# AUDIO_AMP_PT2300.net
KiCad netlist of a schematic drawn in Altium Designer
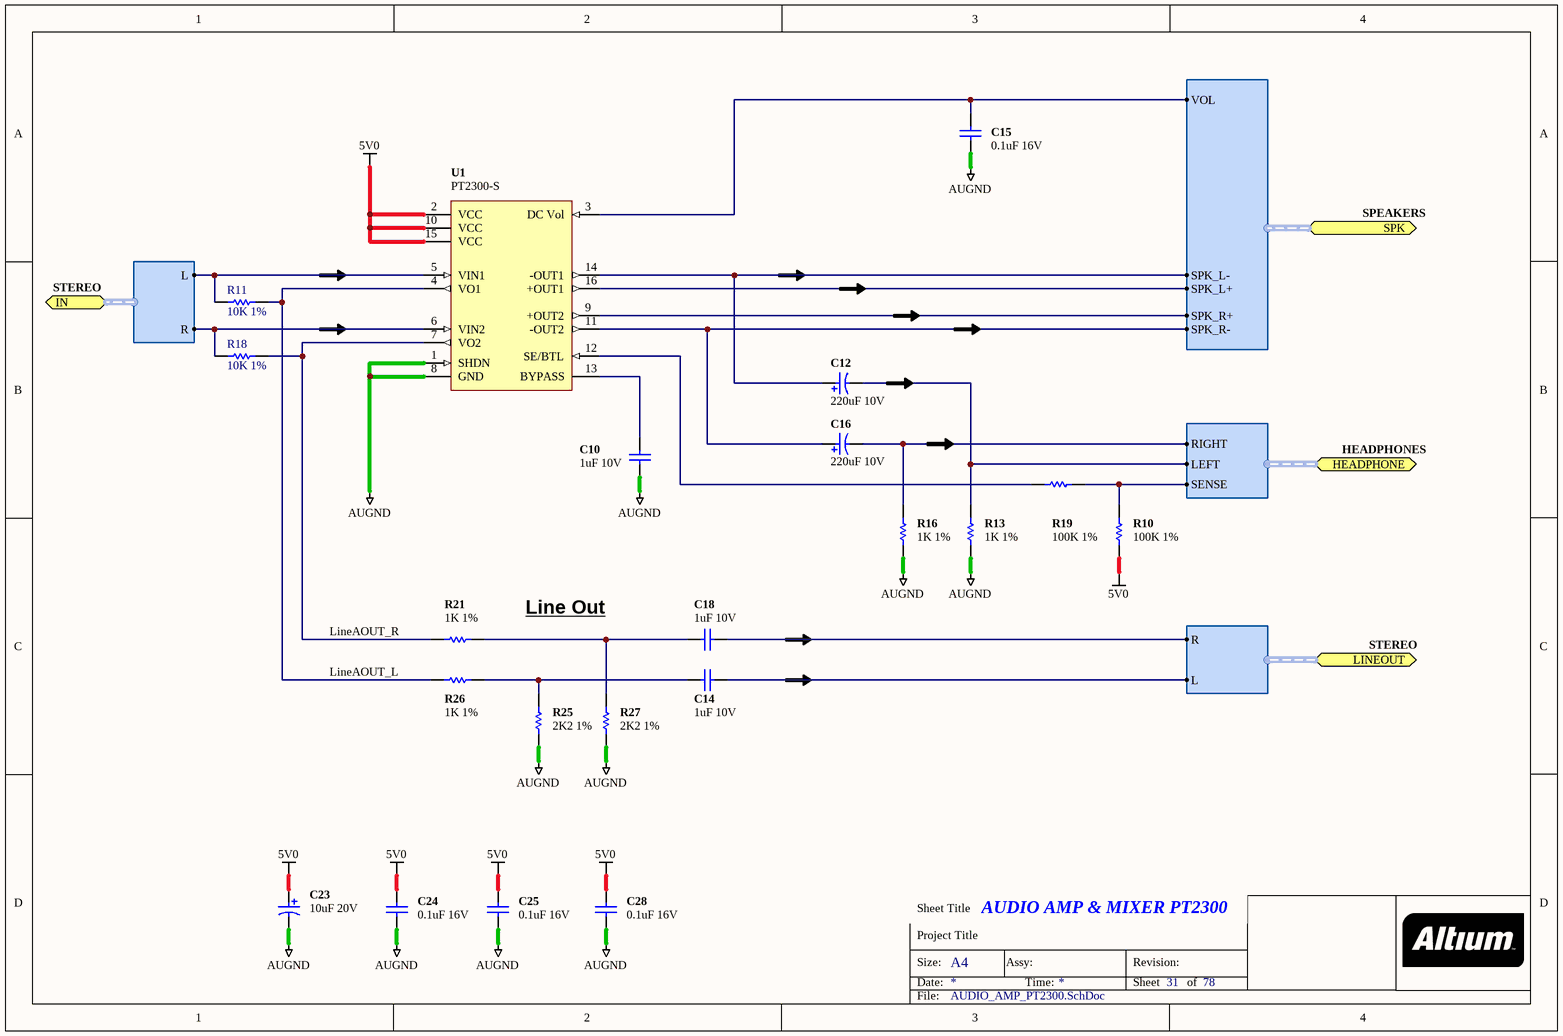
[diagram p0: AUDIO_AMP_PT2300.SchDoc]

(export (version "E")
  (design (tool "Eeschema 10.0.6"))
  (components
    (comp (ref "C10")
      (value "1uF 10V")
      (footprint "CAPC1005-STAR")
      (description "Capacitor, Ceramic, 1uF 10% 10V 0402 (1005) X5R")
      (fields (field (name "TOLERANCE") "10 %"))
      (libsource (lib "AltiumDesignLibrary") (part "CAP-NP"))
    )
    (comp (ref "C12")
      (value "220uF 10V")
      (footprint "CAPC7343-STAR")
      (description "Capacitor, Tantalum, 220uF 10% 10V MCCT-D (7343-31)")
      (fields (field (name "TOLERANCE") "10 %"))
      (libsource (lib "altium-import") (part "root_1_CAP-P_"))
    )
    (comp (ref "C14")
      (value "1uF 10V")
      (footprint "CAPC1005-STAR")
      (description "Capacitor, Ceramic, 1uF 10% 10V 0402 (1005) X5R")
      (fields (field (name "TOLERANCE") "10 %"))
      (libsource (lib "AltiumDesignLibrary") (part "CAP-NP"))
    )
    (comp (ref "C15")
      (value "0.1uF 16V")
      (footprint "CAPC1005-STAR")
      (description "Capacitor, Ceramic, 0.1uF 10% 16V 0402 (1005) X7R")
      (fields (field (name "TOLERANCE") "10 %"))
      (libsource (lib "altium-import") (part "root_2_CAP-NP_"))
    )
    (comp (ref "C16")
      (value "220uF 10V")
      (footprint "CAPC7343-STAR")
      (description "Capacitor, Tantalum, 220uF 10% 10V MCCT-D (7343-31)")
      (fields (field (name "TOLERANCE") "10 %"))
      (libsource (lib "altium-import") (part "root_1_CAP-P_"))
    )
    (comp (ref "C18")
      (value "1uF 10V")
      (footprint "CAPC1005-STAR")
      (description "Capacitor, Ceramic, 1uF 10% 10V 0402 (1005) X5R")
      (fields (field (name "TOLERANCE") "10 %"))
      (libsource (lib "AltiumDesignLibrary") (part "CAP-NP"))
    )
    (comp (ref "C23")
      (value "10uF 20V")
      (footprint "CAPC3528-STAR")
      (description "Capacitor, Tantalum, 10uF 10% 20V MCCT-B (3528)")
      (fields (field (name "TOLERANCE") "10 %"))
      (libsource (lib "altium-import") (part "root_0_mirrored_CAP-P_"))
    )
    (comp (ref "C24")
      (value "0.1uF 16V")
      (footprint "CAPC1005-STAR")
      (description "Capacitor, Ceramic, 0.1uF 10% 16V 0402 (1005) X7R")
      (fields (field (name "TOLERANCE") "10 %"))
      (libsource (lib "altium-import") (part "root_2_CAP-NP_"))
    )
    (comp (ref "C25")
      (value "0.1uF 16V")
      (footprint "CAPC1005-STAR")
      (description "Capacitor, Ceramic, 0.1uF 10% 16V 0402 (1005) X7R")
      (fields (field (name "TOLERANCE") "10 %"))
      (libsource (lib "altium-import") (part "root_2_CAP-NP_"))
    )
    (comp (ref "C28")
      (value "0.1uF 16V")
      (footprint "CAPC1005-STAR")
      (description "Capacitor, Ceramic, 0.1uF 10% 16V 0402 (1005) X7R")
      (fields (field (name "TOLERANCE") "10 %"))
      (libsource (lib "altium-import") (part "root_2_CAP-NP_"))
    )
    (comp (ref "R10")
      (value "100K 1%")
      (footprint "RESC1005-STAR")
      (description "Resistor, 100K 1% 0402 (1005)")
      (fields (field (name "TOLERANCE") "1 %"))
      (libsource (lib "altium-import") (part "root_0_RES_"))
    )
    (comp (ref "R11")
      (value "10K 1%")
      (footprint "RESC1005-STAR")
      (description "Resistor, 10K 1% 0402 (1005)")
      (fields (field (name "TOLERANCE") "1%"))
      (libsource (lib "AltiumDesignLibrary") (part "RES"))
    )
    (comp (ref "R13")
      (value "1K 1%")
      (footprint "RESC1005-STAR")
      (description "Resistor, 1K 1% 0402 (1005)")
      (fields (field (name "TOLERANCE") "1 %"))
      (libsource (lib "altium-import") (part "root_2_RES_"))
    )
    (comp (ref "R16")
      (value "1K 1%")
      (footprint "RESC1005-STAR")
      (description "Resistor, 1K 1% 0402 (1005)")
      (fields (field (name "TOLERANCE") "1 %"))
      (libsource (lib "altium-import") (part "root_2_RES_"))
    )
    (comp (ref "R18")
      (value "10K 1%")
      (footprint "RESC1005-STAR")
      (description "Resistor, 10K 1% 0402 (1005)")
      (fields (field (name "TOLERANCE") "1%"))
      (libsource (lib "AltiumDesignLibrary") (part "RES"))
    )
    (comp (ref "R19")
      (value "100K 1%")
      (footprint "RESC1005-STAR")
      (description "Resistor, 100K 1% 0402 (1005)")
      (fields (field (name "TOLERANCE") "1 %"))
      (libsource (lib "altium-import") (part "root_1_RES_"))
    )
    (comp (ref "R21")
      (value "1K 1%")
      (footprint "RESC1005-STAR")
      (description "Resistor, 1K 1% 0402 (1005)")
      (fields (field (name "TOLERANCE") "1 %"))
      (libsource (lib "altium-import") (part "root_1_RES_"))
    )
    (comp (ref "R25")
      (value "2K2 1%")
      (footprint "RESC1005-STAR")
      (description "Resistor, 2K2 1% 0402 (1005)")
      (fields (field (name "TOLERANCE") "1 %"))
      (libsource (lib "altium-import") (part "root_2_RES_"))
    )
    (comp (ref "R26")
      (value "1K 1%")
      (footprint "RESC1005-STAR")
      (description "Resistor, 1K 1% 0402 (1005)")
      (fields (field (name "TOLERANCE") "1 %"))
      (libsource (lib "altium-import") (part "root_1_RES_"))
    )
    (comp (ref "R27")
      (value "2K2 1%")
      (footprint "RESC1005-STAR")
      (description "Resistor, 2K2 1% 0402 (1005)")
      (fields (field (name "TOLERANCE") "1 %"))
      (libsource (lib "altium-import") (part "root_0_RES_"))
    )
    (comp (ref "U1")
      (value "PT2300-S")
      (footprint "SOIC127P1030-16N")
      (description "PT2300, 2W x 2 Class AB Audio Power Amplifier")
      (libsource (lib "AltiumDesignLibrary") (part "PT2300-16"))
    )
  )
  (nets
    (net (code "4") (name "/LEFT") (class "Default")
      (node (ref "C12") (pin "2") (pinfunction "2_2") (pintype "passive"))
      (node (ref "R13") (pin "2") (pinfunction "2_2") (pintype "passive"))
    )
    (net (code "5") (name "/LineAOUT_L") (class "Default")
      (node (ref "R11") (pin "2") (pinfunction "2_2") (pintype "passive"))
      (node (ref "R26") (pin "1") (pinfunction "1_1") (pintype "passive"))
      (node (ref "U1") (pin "4") (pinfunction "VO1_4") (pintype "output"))
    )
    (net (code "6") (name "/LineAOUT_R") (class "Default")
      (node (ref "R18") (pin "2") (pinfunction "2_2") (pintype "passive"))
      (node (ref "R21") (pin "1") (pinfunction "1_1") (pintype "passive"))
      (node (ref "U1") (pin "7") (pinfunction "VO2_7") (pintype "output"))
    )
    (net (code "7") (name "/RIGHT") (class "Default")
      (node (ref "C16") (pin "2") (pinfunction "2_2") (pintype "passive"))
      (node (ref "R16") (pin "2") (pinfunction "2_2") (pintype "passive"))
    )
    (net (code "8") (name "/SENSE") (class "Default")
      (node (ref "R10") (pin "1") (pinfunction "1_1") (pintype "passive"))
      (node (ref "R19") (pin "2") (pinfunction "2_2") (pintype "passive"))
    )
    (net (code "9") (name "/SPK_L+") (class "Default")
      (node (ref "U1") (pin "16") (pinfunction "+OUT1_16") (pintype "output"))
    )
    (net (code "10") (name "/SPK_L-") (class "Default")
      (node (ref "C12") (pin "1") (pinfunction "1_1") (pintype "passive"))
      (node (ref "U1") (pin "14") (pinfunction "-OUT1_14") (pintype "output"))
    )
    (net (code "11") (name "/SPK_R+") (class "Default")
      (node (ref "U1") (pin "9") (pinfunction "+OUT2_9") (pintype "output"))
    )
    (net (code "12") (name "/SPK_R-") (class "Default")
      (node (ref "C16") (pin "1") (pinfunction "1_1") (pintype "passive"))
      (node (ref "U1") (pin "11") (pinfunction "-OUT2_11") (pintype "output"))
    )
    (net (code "13") (name "/VOL") (class "Default")
      (node (ref "C15") (pin "2") (pinfunction "2_2") (pintype "passive"))
      (node (ref "U1") (pin "3") (pinfunction "DC_Vol_3") (pintype "input"))
    )
    (net (code "17") (name "5V0") (class "Default")
      (node (ref "C23") (pin "1") (pinfunction "1_1") (pintype "passive"))
      (node (ref "C24") (pin "2") (pinfunction "2_2") (pintype "passive"))
      (node (ref "C25") (pin "2") (pinfunction "2_2") (pintype "passive"))
      (node (ref "C28") (pin "2") (pinfunction "2_2") (pintype "passive"))
      (node (ref "R10") (pin "2") (pinfunction "2_2") (pintype "passive"))
      (node (ref "U1") (pin "10") (pinfunction "VCC_10") (pintype "power_in"))
      (node (ref "U1") (pin "15") (pinfunction "VCC_15") (pintype "power_in"))
      (node (ref "U1") (pin "2") (pinfunction "VCC_2") (pintype "power_in"))
    )
    (net (code "18") (name "AUGND") (class "Default")
      (node (ref "C10") (pin "2") (pinfunction "2_2") (pintype "passive"))
      (node (ref "C15") (pin "1") (pinfunction "1_1") (pintype "passive"))
      (node (ref "C23") (pin "2") (pinfunction "2_2") (pintype "passive"))
      (node (ref "C24") (pin "1") (pinfunction "1_1") (pintype "passive"))
      (node (ref "C25") (pin "1") (pinfunction "1_1") (pintype "passive"))
      (node (ref "C28") (pin "1") (pinfunction "1_1") (pintype "passive"))
      (node (ref "R13") (pin "1") (pinfunction "1_1") (pintype "passive"))
      (node (ref "R16") (pin "1") (pinfunction "1_1") (pintype "passive"))
      (node (ref "R25") (pin "1") (pinfunction "1_1") (pintype "passive"))
      (node (ref "R27") (pin "2") (pinfunction "2_2") (pintype "passive"))
      (node (ref "U1") (pin "1") (pinfunction "SHDN_1") (pintype "input"))
      (node (ref "U1") (pin "8") (pinfunction "GND_8") (pintype "power_in"))
    )
    (net (code "19") (name "Net-(C14-Pad1)") (class "Default")
      (node (ref "C14") (pin "1") (pinfunction "1_1") (pintype "passive"))
      (node (ref "R25") (pin "2") (pinfunction "2_2") (pintype "passive"))
      (node (ref "R26") (pin "2") (pinfunction "2_2") (pintype "passive"))
    )
    (net (code "20") (name "Net-(C18-Pad2)") (class "Default")
      (node (ref "C18") (pin "2") (pinfunction "2_2") (pintype "passive"))
      (node (ref "R21") (pin "2") (pinfunction "2_2") (pintype "passive"))
      (node (ref "R27") (pin "1") (pinfunction "1_1") (pintype "passive"))
    )
    (net (code "21") (name "Net-(U1-BYPASS)") (class "Default")
      (node (ref "C10") (pin "1") (pinfunction "1_1") (pintype "passive"))
      (node (ref "U1") (pin "13") (pinfunction "BYPASS_13") (pintype "passive"))
    )
    (net (code "22") (name "Net-(U1-SE{slash}BTL)") (class "Default")
      (node (ref "R19") (pin "1") (pinfunction "1_1") (pintype "passive"))
      (node (ref "U1") (pin "12") (pinfunction "SE/BTL_12") (pintype "input"))
    )
    (net (code "23") (name "Net-(U1-VIN1)") (class "Default")
      (node (ref "R11") (pin "1") (pinfunction "1_1") (pintype "passive"))
      (node (ref "U1") (pin "5") (pinfunction "VIN1_5") (pintype "input"))
    )
    (net (code "24") (name "Net-(U1-VIN2)") (class "Default")
      (node (ref "R18") (pin "1") (pinfunction "1_1") (pintype "passive"))
      (node (ref "U1") (pin "6") (pinfunction "VIN2_6") (pintype "input"))
    )
    (net (code "25") (name "unconnected-(C14-Pad2)") (class "Default")
      (node (ref "C14") (pin "2") (pinfunction "2_2") (pintype "passive"))
    )
    (net (code "26") (name "unconnected-(C18-Pad1)") (class "Default")
      (node (ref "C18") (pin "1") (pinfunction "1_1") (pintype "passive"))
    )
  )
)
